# Adapters.net
KiCad netlist of a schematic drawn in Altium Designer
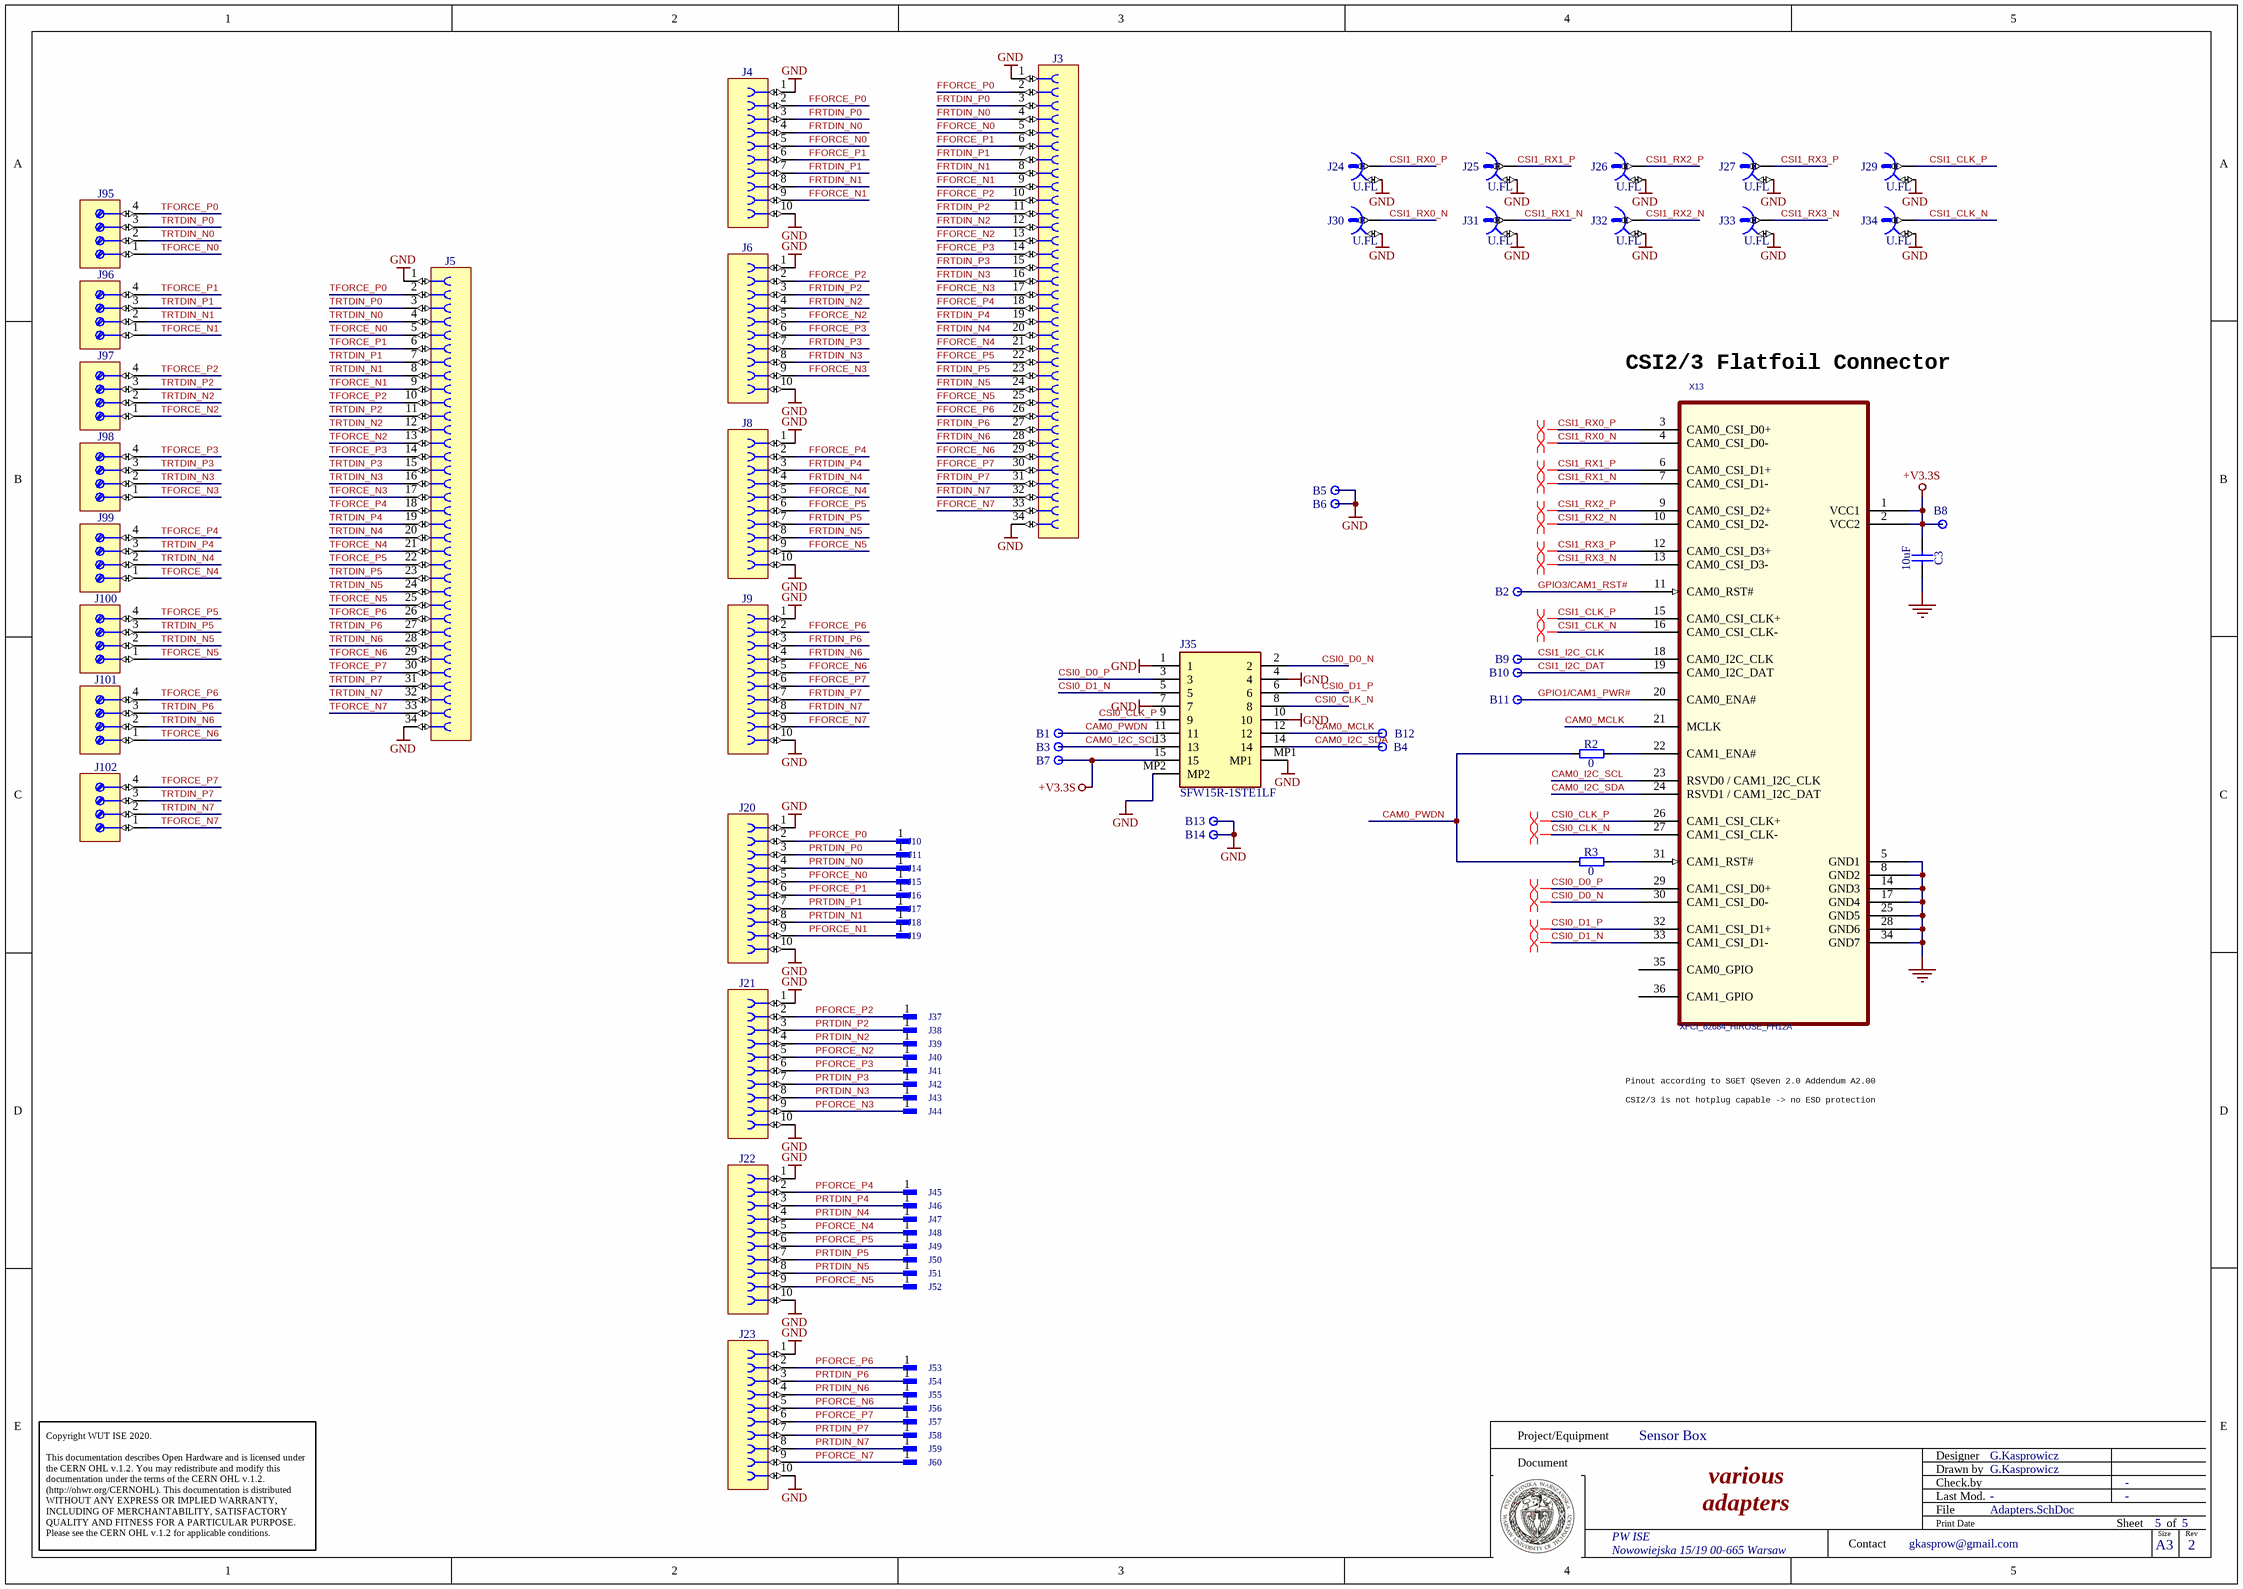
[diagram p0: Adapters.SchDoc]

(export (version "E")
  (design (tool "Eeschema 10.0.6"))
  (components
    (comp (ref "B1")
      (value "Plated Hole")
      (footprint "c130h80")
      (description "Single Terminal Socket")
      (fields (field (name "PART NUMBER") "PLATED_HOLE0.8_PAD1.3"))
      (libsource (lib "Eletro-mechanical") (part "Single Terminal Socket"))
    )
    (comp (ref "B2")
      (value "Plated Hole")
      (footprint "c130h80")
      (description "Single Terminal Socket")
      (fields (field (name "PART NUMBER") "PLATED_HOLE0.8_PAD1.3"))
      (libsource (lib "Eletro-mechanical") (part "Single Terminal Socket"))
    )
    (comp (ref "B3")
      (value "Plated Hole")
      (footprint "c130h80")
      (description "Single Terminal Socket")
      (fields (field (name "PART NUMBER") "PLATED_HOLE0.8_PAD1.3"))
      (libsource (lib "Eletro-mechanical") (part "Single Terminal Socket"))
    )
    (comp (ref "B4")
      (value "Plated Hole")
      (footprint "c130h80")
      (description "Single Terminal Socket")
      (fields (field (name "PART NUMBER") "PLATED_HOLE0.8_PAD1.3"))
      (libsource (lib "Eletro-mechanical") (part "Single Terminal Socket"))
    )
    (comp (ref "B5")
      (value "Plated Hole")
      (footprint "c130h80")
      (description "Single Terminal Socket")
      (fields (field (name "PART NUMBER") "PLATED_HOLE0.8_PAD1.3"))
      (libsource (lib "Eletro-mechanical") (part "Single Terminal Socket"))
    )
    (comp (ref "B6")
      (value "Plated Hole")
      (footprint "c130h80")
      (description "Single Terminal Socket")
      (fields (field (name "PART NUMBER") "PLATED_HOLE0.8_PAD1.3"))
      (libsource (lib "Eletro-mechanical") (part "Single Terminal Socket"))
    )
    (comp (ref "B7")
      (value "Plated Hole")
      (footprint "c130h80")
      (description "Single Terminal Socket")
      (fields (field (name "PART NUMBER") "PLATED_HOLE0.8_PAD1.3"))
      (libsource (lib "Eletro-mechanical") (part "Single Terminal Socket"))
    )
    (comp (ref "B8")
      (value "Plated Hole")
      (footprint "c130h80")
      (description "Single Terminal Socket")
      (fields (field (name "PART NUMBER") "PLATED_HOLE0.8_PAD1.3"))
      (libsource (lib "Eletro-mechanical") (part "Single Terminal Socket"))
    )
    (comp (ref "B9")
      (value "Plated Hole")
      (footprint "c130h80")
      (description "Single Terminal Socket")
      (fields (field (name "PART NUMBER") "PLATED_HOLE0.8_PAD1.3"))
      (libsource (lib "Eletro-mechanical") (part "Single Terminal Socket"))
    )
    (comp (ref "B10")
      (value "Plated Hole")
      (footprint "c130h80")
      (description "Single Terminal Socket")
      (fields (field (name "PART NUMBER") "PLATED_HOLE0.8_PAD1.3"))
      (libsource (lib "Eletro-mechanical") (part "Single Terminal Socket"))
    )
    (comp (ref "B11")
      (value "Plated Hole")
      (footprint "c130h80")
      (description "Single Terminal Socket")
      (fields (field (name "PART NUMBER") "PLATED_HOLE0.8_PAD1.3"))
      (libsource (lib "Eletro-mechanical") (part "Single Terminal Socket"))
    )
    (comp (ref "B12")
      (value "Plated Hole")
      (footprint "c130h80")
      (description "Single Terminal Socket")
      (fields (field (name "PART NUMBER") "PLATED_HOLE0.8_PAD1.3"))
      (libsource (lib "Eletro-mechanical") (part "Single Terminal Socket"))
    )
    (comp (ref "B13")
      (value "Plated Hole")
      (footprint "c130h80")
      (description "Single Terminal Socket")
      (fields (field (name "PART NUMBER") "PLATED_HOLE0.8_PAD1.3"))
      (libsource (lib "Eletro-mechanical") (part "Single Terminal Socket"))
    )
    (comp (ref "B14")
      (value "Plated Hole")
      (footprint "c130h80")
      (description "Single Terminal Socket")
      (fields (field (name "PART NUMBER") "PLATED_HOLE0.8_PAD1.3"))
      (libsource (lib "Eletro-mechanical") (part "Single Terminal Socket"))
    )
    (comp (ref "C3")
      (value "10uF")
      (footprint "CAPC2012X135N")
      (description "Non-polarised capacitor")
      (fields (field (name "PART NUMBER") "CC0805_10UF_16V_10%_X5R") (field (name "VOLTAGE") "16V"))
      (libsource (lib "Capacitors") (part "Capacitor - non polarized"))
    )
    (comp (ref "J3")
      (value "Socket 34")
      (footprint "3M_9134-4500PL")
      (description "Connector 34 Female")
      (fields (field (name "PART NUMBER") "3M_9134-4500PL") (field (name "MANUFACTURER") "3M"))
      (libsource (lib "Connectors") (part "Connector 34 Female"))
    )
    (comp (ref "J4")
      (value "FFC/FPC")
      (footprint "MOLEX_52745-1097")
      (description "Connector 10 Female")
      (fields (field (name "PART NUMBER") "MOLEX_52745-1097") (field (name "MANUFACTURER") "MOLEX"))
      (libsource (lib "Connectors") (part "Connector 10 Female"))
    )
    (comp (ref "J5")
      (value "Socket 34")
      (footprint "3M_9134-4500PL")
      (description "Connector 34 Female")
      (fields (field (name "PART NUMBER") "3M_9134-4500PL") (field (name "MANUFACTURER") "3M"))
      (libsource (lib "Connectors") (part "Connector 34 Female"))
    )
    (comp (ref "J6")
      (value "FFC/FPC")
      (footprint "MOLEX_52745-1097")
      (description "Connector 10 Female")
      (fields (field (name "PART NUMBER") "MOLEX_52745-1097") (field (name "MANUFACTURER") "MOLEX"))
      (libsource (lib "Connectors") (part "Connector 10 Female"))
    )
    (comp (ref "J8")
      (value "FFC/FPC")
      (footprint "MOLEX_52745-1097")
      (description "Connector 10 Female")
      (fields (field (name "PART NUMBER") "MOLEX_52745-1097") (field (name "MANUFACTURER") "MOLEX"))
      (libsource (lib "Connectors") (part "Connector 10 Female"))
    )
    (comp (ref "J9")
      (value "FFC/FPC")
      (footprint "MOLEX_52745-1097")
      (description "Connector 10 Female")
      (fields (field (name "PART NUMBER") "MOLEX_52745-1097") (field (name "MANUFACTURER") "MOLEX"))
      (libsource (lib "Connectors") (part "Connector 10 Female"))
    )
    (comp (ref "J10")
      (value "SMD Pad")
      (footprint "R350X200")
      (description "Single SMD Pad")
      (fields (field (name "PART NUMBER") "SMD_PAD_3.5X2MM"))
      (libsource (lib "Eletro-mechanical") (part "Single SMD Pad"))
    )
    (comp (ref "J11")
      (value "SMD Pad")
      (footprint "R350X200")
      (description "Single SMD Pad")
      (fields (field (name "PART NUMBER") "SMD_PAD_3.5X2MM"))
      (libsource (lib "Eletro-mechanical") (part "Single SMD Pad"))
    )
    (comp (ref "J14")
      (value "SMD Pad")
      (footprint "R350X200")
      (description "Single SMD Pad")
      (fields (field (name "PART NUMBER") "SMD_PAD_3.5X2MM"))
      (libsource (lib "Eletro-mechanical") (part "Single SMD Pad"))
    )
    (comp (ref "J15")
      (value "SMD Pad")
      (footprint "R350X200")
      (description "Single SMD Pad")
      (fields (field (name "PART NUMBER") "SMD_PAD_3.5X2MM"))
      (libsource (lib "Eletro-mechanical") (part "Single SMD Pad"))
    )
    (comp (ref "J16")
      (value "SMD Pad")
      (footprint "R350X200")
      (description "Single SMD Pad")
      (fields (field (name "PART NUMBER") "SMD_PAD_3.5X2MM"))
      (libsource (lib "Eletro-mechanical") (part "Single SMD Pad"))
    )
    (comp (ref "J17")
      (value "SMD Pad")
      (footprint "R350X200")
      (description "Single SMD Pad")
      (fields (field (name "PART NUMBER") "SMD_PAD_3.5X2MM"))
      (libsource (lib "Eletro-mechanical") (part "Single SMD Pad"))
    )
    (comp (ref "J18")
      (value "SMD Pad")
      (footprint "R350X200")
      (description "Single SMD Pad")
      (fields (field (name "PART NUMBER") "SMD_PAD_3.5X2MM"))
      (libsource (lib "Eletro-mechanical") (part "Single SMD Pad"))
    )
    (comp (ref "J19")
      (value "SMD Pad")
      (footprint "R350X200")
      (description "Single SMD Pad")
      (fields (field (name "PART NUMBER") "SMD_PAD_3.5X2MM"))
      (libsource (lib "Eletro-mechanical") (part "Single SMD Pad"))
    )
    (comp (ref "J20")
      (value "FFC/FPC")
      (footprint "MOLEX_52745-1097")
      (description "Connector 10 Female")
      (fields (field (name "PART NUMBER") "MOLEX_52745-1097") (field (name "MANUFACTURER") "MOLEX"))
      (libsource (lib "Connectors") (part "Connector 10 Female"))
    )
    (comp (ref "J21")
      (value "FFC/FPC")
      (footprint "MOLEX_52745-1097")
      (description "Connector 10 Female")
      (fields (field (name "PART NUMBER") "MOLEX_52745-1097") (field (name "MANUFACTURER") "MOLEX"))
      (libsource (lib "Connectors") (part "Connector 10 Female"))
    )
    (comp (ref "J22")
      (value "FFC/FPC")
      (footprint "MOLEX_52745-1097")
      (description "Connector 10 Female")
      (fields (field (name "PART NUMBER") "MOLEX_52745-1097") (field (name "MANUFACTURER") "MOLEX"))
      (libsource (lib "Connectors") (part "Connector 10 Female"))
    )
    (comp (ref "J23")
      (value "FFC/FPC")
      (footprint "MOLEX_52745-1097")
      (description "Connector 10 Female")
      (fields (field (name "PART NUMBER") "MOLEX_52745-1097") (field (name "MANUFACTURER") "MOLEX"))
      (libsource (lib "Connectors") (part "Connector 10 Female"))
    )
    (comp (ref "J24")
      (value "U.FL")
      (footprint "HIROSE_U.FL-R-SMT-1(10)")
      (fields
        (field (name "PART NUMBER") "HIROSE_U.FL-R-SMT-1(10)")
        (field (name "MANUFACTURER") "HIROSE (HRS)")
        (field (name "MANUFACTURER PART NUMBER") "U.FL-R-SMT-1(10)")
      )
      (libsource (lib "Connectors") (part "Coax_1Male_1Shield"))
    )
    (comp (ref "J25")
      (value "U.FL")
      (footprint "HIROSE_U.FL-R-SMT-1(10)")
      (fields
        (field (name "PART NUMBER") "HIROSE_U.FL-R-SMT-1(10)")
        (field (name "MANUFACTURER") "HIROSE (HRS)")
        (field (name "MANUFACTURER PART NUMBER") "U.FL-R-SMT-1(10)")
      )
      (libsource (lib "Connectors") (part "Coax_1Male_1Shield"))
    )
    (comp (ref "J26")
      (value "U.FL")
      (footprint "HIROSE_U.FL-R-SMT-1(10)")
      (fields
        (field (name "PART NUMBER") "HIROSE_U.FL-R-SMT-1(10)")
        (field (name "MANUFACTURER") "HIROSE (HRS)")
        (field (name "MANUFACTURER PART NUMBER") "U.FL-R-SMT-1(10)")
      )
      (libsource (lib "Connectors") (part "Coax_1Male_1Shield"))
    )
    (comp (ref "J27")
      (value "U.FL")
      (footprint "HIROSE_U.FL-R-SMT-1(10)")
      (fields
        (field (name "PART NUMBER") "HIROSE_U.FL-R-SMT-1(10)")
        (field (name "MANUFACTURER") "HIROSE (HRS)")
        (field (name "MANUFACTURER PART NUMBER") "U.FL-R-SMT-1(10)")
      )
      (libsource (lib "Connectors") (part "Coax_1Male_1Shield"))
    )
    (comp (ref "J29")
      (value "U.FL")
      (footprint "HIROSE_U.FL-R-SMT-1(10)")
      (fields
        (field (name "PART NUMBER") "HIROSE_U.FL-R-SMT-1(10)")
        (field (name "MANUFACTURER") "HIROSE (HRS)")
        (field (name "MANUFACTURER PART NUMBER") "U.FL-R-SMT-1(10)")
      )
      (libsource (lib "Connectors") (part "Coax_1Male_1Shield"))
    )
    (comp (ref "J30")
      (value "U.FL")
      (footprint "HIROSE_U.FL-R-SMT-1(10)")
      (fields
        (field (name "PART NUMBER") "HIROSE_U.FL-R-SMT-1(10)")
        (field (name "MANUFACTURER") "HIROSE (HRS)")
        (field (name "MANUFACTURER PART NUMBER") "U.FL-R-SMT-1(10)")
      )
      (libsource (lib "Connectors") (part "Coax_1Male_1Shield"))
    )
    (comp (ref "J31")
      (value "U.FL")
      (footprint "HIROSE_U.FL-R-SMT-1(10)")
      (fields
        (field (name "PART NUMBER") "HIROSE_U.FL-R-SMT-1(10)")
        (field (name "MANUFACTURER") "HIROSE (HRS)")
        (field (name "MANUFACTURER PART NUMBER") "U.FL-R-SMT-1(10)")
      )
      (libsource (lib "Connectors") (part "Coax_1Male_1Shield"))
    )
    (comp (ref "J32")
      (value "U.FL")
      (footprint "HIROSE_U.FL-R-SMT-1(10)")
      (fields
        (field (name "PART NUMBER") "HIROSE_U.FL-R-SMT-1(10)")
        (field (name "MANUFACTURER") "HIROSE (HRS)")
        (field (name "MANUFACTURER PART NUMBER") "U.FL-R-SMT-1(10)")
      )
      (libsource (lib "Connectors") (part "Coax_1Male_1Shield"))
    )
    (comp (ref "J33")
      (value "U.FL")
      (footprint "HIROSE_U.FL-R-SMT-1(10)")
      (fields
        (field (name "PART NUMBER") "HIROSE_U.FL-R-SMT-1(10)")
        (field (name "MANUFACTURER") "HIROSE (HRS)")
        (field (name "MANUFACTURER PART NUMBER") "U.FL-R-SMT-1(10)")
      )
      (libsource (lib "Connectors") (part "Coax_1Male_1Shield"))
    )
    (comp (ref "J34")
      (value "U.FL")
      (footprint "HIROSE_U.FL-R-SMT-1(10)")
      (fields
        (field (name "PART NUMBER") "HIROSE_U.FL-R-SMT-1(10)")
        (field (name "MANUFACTURER") "HIROSE (HRS)")
        (field (name "MANUFACTURER PART NUMBER") "U.FL-R-SMT-1(10)")
      )
      (libsource (lib "Connectors") (part "Coax_1Male_1Shield"))
    )
    (comp (ref "J35")
      (value "SFW15R-1STE1LF")
      (footprint "SamacSys:SFW15R1STE1LF")
      (description "Connector")
      (fields
        (field (name "MOUSER PART NUMBER") "649-SFW15R-1STE1LF")
        (field (name "RS PART NUMBER") "1822728")
      )
      (libsource (lib "*") (part "SFW15R-1STE1LF"))
    )
    (comp (ref "J37")
      (value "SMD Pad")
      (footprint "R350X200")
      (description "Single SMD Pad")
      (fields (field (name "PART NUMBER") "SMD_PAD_3.5X2MM"))
      (libsource (lib "Eletro-mechanical") (part "Single SMD Pad"))
    )
    (comp (ref "J38")
      (value "SMD Pad")
      (footprint "R350X200")
      (description "Single SMD Pad")
      (fields (field (name "PART NUMBER") "SMD_PAD_3.5X2MM"))
      (libsource (lib "Eletro-mechanical") (part "Single SMD Pad"))
    )
    (comp (ref "J39")
      (value "SMD Pad")
      (footprint "R350X200")
      (description "Single SMD Pad")
      (fields (field (name "PART NUMBER") "SMD_PAD_3.5X2MM"))
      (libsource (lib "Eletro-mechanical") (part "Single SMD Pad"))
    )
    (comp (ref "J40")
      (value "SMD Pad")
      (footprint "R350X200")
      (description "Single SMD Pad")
      (fields (field (name "PART NUMBER") "SMD_PAD_3.5X2MM"))
      (libsource (lib "Eletro-mechanical") (part "Single SMD Pad"))
    )
    (comp (ref "J41")
      (value "SMD Pad")
      (footprint "R350X200")
      (description "Single SMD Pad")
      (fields (field (name "PART NUMBER") "SMD_PAD_3.5X2MM"))
      (libsource (lib "Eletro-mechanical") (part "Single SMD Pad"))
    )
    (comp (ref "J42")
      (value "SMD Pad")
      (footprint "R350X200")
      (description "Single SMD Pad")
      (fields (field (name "PART NUMBER") "SMD_PAD_3.5X2MM"))
      (libsource (lib "Eletro-mechanical") (part "Single SMD Pad"))
    )
    (comp (ref "J43")
      (value "SMD Pad")
      (footprint "R350X200")
      (description "Single SMD Pad")
      (fields (field (name "PART NUMBER") "SMD_PAD_3.5X2MM"))
      (libsource (lib "Eletro-mechanical") (part "Single SMD Pad"))
    )
    (comp (ref "J44")
      (value "SMD Pad")
      (footprint "R350X200")
      (description "Single SMD Pad")
      (fields (field (name "PART NUMBER") "SMD_PAD_3.5X2MM"))
      (libsource (lib "Eletro-mechanical") (part "Single SMD Pad"))
    )
    (comp (ref "J45")
      (value "SMD Pad")
      (footprint "R350X200")
      (description "Single SMD Pad")
      (fields (field (name "PART NUMBER") "SMD_PAD_3.5X2MM"))
      (libsource (lib "Eletro-mechanical") (part "Single SMD Pad"))
    )
    (comp (ref "J46")
      (value "SMD Pad")
      (footprint "R350X200")
      (description "Single SMD Pad")
      (fields (field (name "PART NUMBER") "SMD_PAD_3.5X2MM"))
      (libsource (lib "Eletro-mechanical") (part "Single SMD Pad"))
    )
    (comp (ref "J47")
      (value "SMD Pad")
      (footprint "R350X200")
      (description "Single SMD Pad")
      (fields (field (name "PART NUMBER") "SMD_PAD_3.5X2MM"))
      (libsource (lib "Eletro-mechanical") (part "Single SMD Pad"))
    )
    (comp (ref "J48")
      (value "SMD Pad")
      (footprint "R350X200")
      (description "Single SMD Pad")
      (fields (field (name "PART NUMBER") "SMD_PAD_3.5X2MM"))
      (libsource (lib "Eletro-mechanical") (part "Single SMD Pad"))
    )
    (comp (ref "J49")
      (value "SMD Pad")
      (footprint "R350X200")
      (description "Single SMD Pad")
      (fields (field (name "PART NUMBER") "SMD_PAD_3.5X2MM"))
      (libsource (lib "Eletro-mechanical") (part "Single SMD Pad"))
    )
    (comp (ref "J50")
      (value "SMD Pad")
      (footprint "R350X200")
      (description "Single SMD Pad")
      (fields (field (name "PART NUMBER") "SMD_PAD_3.5X2MM"))
      (libsource (lib "Eletro-mechanical") (part "Single SMD Pad"))
    )
    (comp (ref "J51")
      (value "SMD Pad")
      (footprint "R350X200")
      (description "Single SMD Pad")
      (fields (field (name "PART NUMBER") "SMD_PAD_3.5X2MM"))
      (libsource (lib "Eletro-mechanical") (part "Single SMD Pad"))
    )
    (comp (ref "J52")
      (value "SMD Pad")
      (footprint "R350X200")
      (description "Single SMD Pad")
      (fields (field (name "PART NUMBER") "SMD_PAD_3.5X2MM"))
      (libsource (lib "Eletro-mechanical") (part "Single SMD Pad"))
    )
    (comp (ref "J53")
      (value "SMD Pad")
      (footprint "R350X200")
      (description "Single SMD Pad")
      (fields (field (name "PART NUMBER") "SMD_PAD_3.5X2MM"))
      (libsource (lib "Eletro-mechanical") (part "Single SMD Pad"))
    )
    (comp (ref "J54")
      (value "SMD Pad")
      (footprint "R350X200")
      (description "Single SMD Pad")
      (fields (field (name "PART NUMBER") "SMD_PAD_3.5X2MM"))
      (libsource (lib "Eletro-mechanical") (part "Single SMD Pad"))
    )
    (comp (ref "J55")
      (value "SMD Pad")
      (footprint "R350X200")
      (description "Single SMD Pad")
      (fields (field (name "PART NUMBER") "SMD_PAD_3.5X2MM"))
      (libsource (lib "Eletro-mechanical") (part "Single SMD Pad"))
    )
    (comp (ref "J56")
      (value "SMD Pad")
      (footprint "R350X200")
      (description "Single SMD Pad")
      (fields (field (name "PART NUMBER") "SMD_PAD_3.5X2MM"))
      (libsource (lib "Eletro-mechanical") (part "Single SMD Pad"))
    )
    (comp (ref "J57")
      (value "SMD Pad")
      (footprint "R350X200")
      (description "Single SMD Pad")
      (fields (field (name "PART NUMBER") "SMD_PAD_3.5X2MM"))
      (libsource (lib "Eletro-mechanical") (part "Single SMD Pad"))
    )
    (comp (ref "J58")
      (value "SMD Pad")
      (footprint "R350X200")
      (description "Single SMD Pad")
      (fields (field (name "PART NUMBER") "SMD_PAD_3.5X2MM"))
      (libsource (lib "Eletro-mechanical") (part "Single SMD Pad"))
    )
    (comp (ref "J59")
      (value "SMD Pad")
      (footprint "R350X200")
      (description "Single SMD Pad")
      (fields (field (name "PART NUMBER") "SMD_PAD_3.5X2MM"))
      (libsource (lib "Eletro-mechanical") (part "Single SMD Pad"))
    )
    (comp (ref "J60")
      (value "SMD Pad")
      (footprint "R350X200")
      (description "Single SMD Pad")
      (fields (field (name "PART NUMBER") "SMD_PAD_3.5X2MM"))
      (libsource (lib "Eletro-mechanical") (part "Single SMD Pad"))
    )
    (comp (ref "J95")
      (value "~")
      (footprint "PHOENIX_1725672")
      (description "Terminal Block, 4 Positions, Screw Connection")
      (fields (field (name "PART NUMBER") "PHOENIX_1725672") (field (name "MANUFACTURER") "PHOENIX CONTACT"))
      (libsource (lib "Connectors") (part "Terminal Block_4 Positions_Screw Connection"))
    )
    (comp (ref "J96")
      (value "~")
      (footprint "PHOENIX_1725672")
      (description "Terminal Block, 4 Positions, Screw Connection")
      (fields (field (name "PART NUMBER") "PHOENIX_1725672") (field (name "MANUFACTURER") "PHOENIX CONTACT"))
      (libsource (lib "Connectors") (part "Terminal Block_4 Positions_Screw Connection"))
    )
    (comp (ref "J97")
      (value "~")
      (footprint "PHOENIX_1725672")
      (description "Terminal Block, 4 Positions, Screw Connection")
      (fields (field (name "PART NUMBER") "PHOENIX_1725672") (field (name "MANUFACTURER") "PHOENIX CONTACT"))
      (libsource (lib "Connectors") (part "Terminal Block_4 Positions_Screw Connection"))
    )
    (comp (ref "J98")
      (value "~")
      (footprint "PHOENIX_1725672")
      (description "Terminal Block, 4 Positions, Screw Connection")
      (fields (field (name "PART NUMBER") "PHOENIX_1725672") (field (name "MANUFACTURER") "PHOENIX CONTACT"))
      (libsource (lib "Connectors") (part "Terminal Block_4 Positions_Screw Connection"))
    )
    (comp (ref "J99")
      (value "~")
      (footprint "PHOENIX_1725672")
      (description "Terminal Block, 4 Positions, Screw Connection")
      (fields (field (name "PART NUMBER") "PHOENIX_1725672") (field (name "MANUFACTURER") "PHOENIX CONTACT"))
      (libsource (lib "Connectors") (part "Terminal Block_4 Positions_Screw Connection"))
    )
    (comp (ref "J100")
      (value "~")
      (footprint "PHOENIX_1725672")
      (description "Terminal Block, 4 Positions, Screw Connection")
      (fields (field (name "PART NUMBER") "PHOENIX_1725672") (field (name "MANUFACTURER") "PHOENIX CONTACT"))
      (libsource (lib "Connectors") (part "Terminal Block_4 Positions_Screw Connection"))
    )
    (comp (ref "J101")
      (value "~")
      (footprint "PHOENIX_1725672")
      (description "Terminal Block, 4 Positions, Screw Connection")
      (fields (field (name "PART NUMBER") "PHOENIX_1725672") (field (name "MANUFACTURER") "PHOENIX CONTACT"))
      (libsource (lib "Connectors") (part "Terminal Block_4 Positions_Screw Connection"))
    )
    (comp (ref "J102")
      (value "~")
      (footprint "PHOENIX_1725672")
      (description "Terminal Block, 4 Positions, Screw Connection")
      (fields (field (name "PART NUMBER") "PHOENIX_1725672") (field (name "MANUFACTURER") "PHOENIX CONTACT"))
      (libsource (lib "Connectors") (part "Terminal Block_4 Positions_Screw Connection"))
    )
    (comp (ref "R2")
      (value "0")
      (footprint "RESC1005X40N")
      (description "Resistor")
      (fields (field (name "PART NUMBER") "R0402_0R_JUMPER") (field (name "MANUFACTURER") "GENERIC"))
      (libsource (lib "Resistors") (part "Resistor"))
    )
    (comp (ref "R3")
      (value "0")
      (footprint "RESC1005X40N")
      (description "Resistor")
      (fields (field (name "PART NUMBER") "R0402_0R_JUMPER") (field (name "MANUFACTURER") "GENERIC"))
      (libsource (lib "Resistors") (part "Resistor"))
    )
    (comp (ref "X13")
      (value "XFCI_62684_HIROSE_FH12A")
      (footprint "TYCO_3-1734592-6")
      (fields (field (name "PART_NUMBER") "41500541"))
      (libsource (lib "*") (part "SGET_CamConn_FCI_Hirose"))
    )
  )
  (nets
    (net (code "1") (name "+V3.3S") (class "Default")
      (node (ref "B7") (pin "1") (pinfunction "1_1") (pintype "bidirectional"))
      (node (ref "B8") (pin "1") (pinfunction "1_1") (pintype "bidirectional"))
      (node (ref "C3") (pin "1") (pinfunction "1_1") (pintype "passive"))
      (node (ref "J35") (pin "15") (pinfunction "15_15") (pintype "passive"))
      (node (ref "X13") (pin "1") (pinfunction "VCC1_1") (pintype "power_in"))
      (node (ref "X13") (pin "2") (pinfunction "VCC2_2") (pintype "power_in"))
    )
    (net (code "2") (name "/CAM0_I2C_SCL") (class "Default")
      (node (ref "B3") (pin "1") (pinfunction "1_1") (pintype "bidirectional"))
      (node (ref "J35") (pin "13") (pinfunction "13_13") (pintype "passive"))
      (node (ref "X13") (pin "23") (pinfunction "RSVD0_/_CAM1_I2C_CLK_23") (pintype "passive"))
    )
    (net (code "3") (name "/CAM0_I2C_SDA") (class "Default")
      (node (ref "B4") (pin "1") (pinfunction "1_1") (pintype "bidirectional"))
      (node (ref "J35") (pin "14") (pinfunction "14_14") (pintype "passive"))
      (node (ref "X13") (pin "24") (pinfunction "RSVD1_/_CAM1_I2C_DAT_24") (pintype "passive"))
    )
    (net (code "4") (name "/CAM0_MCLK") (class "Default")
      (node (ref "B12") (pin "1") (pinfunction "1_1") (pintype "bidirectional"))
      (node (ref "J35") (pin "12") (pinfunction "12_12") (pintype "passive"))
      (node (ref "X13") (pin "21") (pinfunction "MCLK_21") (pintype "passive"))
    )
    (net (code "5") (name "/CAM0_PWDN") (class "Default")
      (node (ref "B1") (pin "1") (pinfunction "1_1") (pintype "bidirectional"))
      (node (ref "J35") (pin "11") (pinfunction "11_11") (pintype "passive"))
      (node (ref "R2") (pin "1") (pinfunction "1_1") (pintype "passive"))
      (node (ref "R3") (pin "1") (pinfunction "1_1") (pintype "passive"))
    )
    (net (code "6") (name "/CSI0_CLK_N") (class "Default")
      (node (ref "J35") (pin "8") (pinfunction "8_8") (pintype "passive"))
      (node (ref "X13") (pin "27") (pinfunction "CAM1_CSI_CLK-_27") (pintype "passive"))
    )
    (net (code "7") (name "/CSI0_CLK_P") (class "Default")
      (node (ref "J35") (pin "9") (pinfunction "9_9") (pintype "passive"))
      (node (ref "X13") (pin "26") (pinfunction "CAM1_CSI_CLK+_26") (pintype "passive"))
    )
    (net (code "8") (name "/CSI0_D0_N") (class "Default")
      (node (ref "J35") (pin "2") (pinfunction "2_2") (pintype "passive"))
      (node (ref "X13") (pin "30") (pinfunction "CAM1_CSI_D0-_30") (pintype "passive"))
    )
    (net (code "9") (name "/CSI0_D0_P") (class "Default")
      (node (ref "J35") (pin "3") (pinfunction "3_3") (pintype "passive"))
      (node (ref "X13") (pin "29") (pinfunction "CAM1_CSI_D0+_29") (pintype "passive"))
    )
    (net (code "10") (name "/CSI0_D1_N") (class "Default")
      (node (ref "J35") (pin "5") (pinfunction "5_5") (pintype "passive"))
      (node (ref "X13") (pin "33") (pinfunction "CAM1_CSI_D1-_33") (pintype "passive"))
    )
    (net (code "11") (name "/CSI0_D1_P") (class "Default")
      (node (ref "J35") (pin "6") (pinfunction "6_6") (pintype "passive"))
      (node (ref "X13") (pin "32") (pinfunction "CAM1_CSI_D1+_32") (pintype "passive"))
    )
    (net (code "12") (name "/CSI1_CLK_N") (class "Default")
      (node (ref "J34") (pin "1") (pinfunction "1_1") (pintype "bidirectional"))
      (node (ref "X13") (pin "16") (pinfunction "CAM0_CSI_CLK-_16") (pintype "passive"))
    )
    (net (code "13") (name "/CSI1_CLK_P") (class "Default")
      (node (ref "J29") (pin "1") (pinfunction "1_1") (pintype "bidirectional"))
      (node (ref "X13") (pin "15") (pinfunction "CAM0_CSI_CLK+_15") (pintype "passive"))
    )
    (net (code "14") (name "/CSI1_I2C_CLK") (class "Default")
      (node (ref "B9") (pin "1") (pinfunction "1_1") (pintype "bidirectional"))
      (node (ref "X13") (pin "18") (pinfunction "CAM0_I2C_CLK_18") (pintype "passive"))
    )
    (net (code "15") (name "/CSI1_I2C_DAT") (class "Default")
      (node (ref "B10") (pin "1") (pinfunction "1_1") (pintype "bidirectional"))
      (node (ref "X13") (pin "19") (pinfunction "CAM0_I2C_DAT_19") (pintype "passive"))
    )
    (net (code "16") (name "/CSI1_RX0_N") (class "Default")
      (node (ref "J30") (pin "1") (pinfunction "1_1") (pintype "bidirectional"))
      (node (ref "X13") (pin "4") (pinfunction "CAM0_CSI_D0-_4") (pintype "passive"))
    )
    (net (code "17") (name "/CSI1_RX0_P") (class "Default")
      (node (ref "J24") (pin "1") (pinfunction "1_1") (pintype "bidirectional"))
      (node (ref "X13") (pin "3") (pinfunction "CAM0_CSI_D0+_3") (pintype "passive"))
    )
    (net (code "18") (name "/CSI1_RX1_N") (class "Default")
      (node (ref "J31") (pin "1") (pinfunction "1_1") (pintype "bidirectional"))
      (node (ref "X13") (pin "7") (pinfunction "CAM0_CSI_D1-_7") (pintype "passive"))
    )
    (net (code "19") (name "/CSI1_RX1_P") (class "Default")
      (node (ref "J25") (pin "1") (pinfunction "1_1") (pintype "bidirectional"))
      (node (ref "X13") (pin "6") (pinfunction "CAM0_CSI_D1+_6") (pintype "passive"))
    )
    (net (code "20") (name "/CSI1_RX2_N") (class "Default")
      (node (ref "J32") (pin "1") (pinfunction "1_1") (pintype "bidirectional"))
      (node (ref "X13") (pin "10") (pinfunction "CAM0_CSI_D2-_10") (pintype "passive"))
    )
    (net (code "21") (name "/CSI1_RX2_P") (class "Default")
      (node (ref "J26") (pin "1") (pinfunction "1_1") (pintype "bidirectional"))
      (node (ref "X13") (pin "9") (pinfunction "CAM0_CSI_D2+_9") (pintype "passive"))
    )
    (net (code "22") (name "/CSI1_RX3_N") (class "Default")
      (node (ref "J33") (pin "1") (pinfunction "1_1") (pintype "bidirectional"))
      (node (ref "X13") (pin "13") (pinfunction "CAM0_CSI_D3-_13") (pintype "passive"))
    )
    (net (code "23") (name "/CSI1_RX3_P") (class "Default")
      (node (ref "J27") (pin "1") (pinfunction "1_1") (pintype "bidirectional"))
      (node (ref "X13") (pin "12") (pinfunction "CAM0_CSI_D3+_12") (pintype "passive"))
    )
    (net (code "24") (name "/FFORCE_N0") (class "Default")
      (node (ref "J3") (pin "5") (pinfunction "5_5") (pintype "bidirectional"))
      (node (ref "J4") (pin "5") (pinfunction "5_5") (pintype "bidirectional"))
    )
    (net (code "25") (name "/FFORCE_N1") (class "Default")
      (node (ref "J3") (pin "9") (pinfunction "9_9") (pintype "bidirectional"))
      (node (ref "J4") (pin "9") (pinfunction "9_9") (pintype "bidirectional"))
    )
    (net (code "26") (name "/FFORCE_N2") (class "Default")
      (node (ref "J3") (pin "13") (pinfunction "13_13") (pintype "bidirectional"))
      (node (ref "J6") (pin "5") (pinfunction "5_5") (pintype "bidirectional"))
    )
    (net (code "27") (name "/FFORCE_N3") (class "Default")
      (node (ref "J3") (pin "17") (pinfunction "17_17") (pintype "bidirectional"))
      (node (ref "J6") (pin "9") (pinfunction "9_9") (pintype "bidirectional"))
    )
    (net (code "28") (name "/FFORCE_N4") (class "Default")
      (node (ref "J3") (pin "21") (pinfunction "21_21") (pintype "bidirectional"))
      (node (ref "J8") (pin "5") (pinfunction "5_5") (pintype "bidirectional"))
    )
    (net (code "29") (name "/FFORCE_N5") (class "Default")
      (node (ref "J3") (pin "25") (pinfunction "25_25") (pintype "bidirectional"))
      (node (ref "J8") (pin "9") (pinfunction "9_9") (pintype "bidirectional"))
    )
    (net (code "30") (name "/FFORCE_N6") (class "Default")
      (node (ref "J3") (pin "29") (pinfunction "29_29") (pintype "bidirectional"))
      (node (ref "J9") (pin "5") (pinfunction "5_5") (pintype "bidirectional"))
    )
    (net (code "31") (name "/FFORCE_N7") (class "Default")
      (node (ref "J3") (pin "33") (pinfunction "33_33") (pintype "bidirectional"))
      (node (ref "J9") (pin "9") (pinfunction "9_9") (pintype "bidirectional"))
    )
    (net (code "32") (name "/FFORCE_P0") (class "Default")
      (node (ref "J3") (pin "2") (pinfunction "2_2") (pintype "bidirectional"))
      (node (ref "J4") (pin "2") (pinfunction "2_2") (pintype "bidirectional"))
    )
    (net (code "33") (name "/FFORCE_P1") (class "Default")
      (node (ref "J3") (pin "6") (pinfunction "6_6") (pintype "bidirectional"))
      (node (ref "J4") (pin "6") (pinfunction "6_6") (pintype "bidirectional"))
    )
    (net (code "34") (name "/FFORCE_P2") (class "Default")
      (node (ref "J3") (pin "10") (pinfunction "10_10") (pintype "bidirectional"))
      (node (ref "J6") (pin "2") (pinfunction "2_2") (pintype "bidirectional"))
    )
    (net (code "35") (name "/FFORCE_P3") (class "Default")
      (node (ref "J3") (pin "14") (pinfunction "14_14") (pintype "bidirectional"))
      (node (ref "J6") (pin "6") (pinfunction "6_6") (pintype "bidirectional"))
    )
    (net (code "36") (name "/FFORCE_P4") (class "Default")
      (node (ref "J3") (pin "18") (pinfunction "18_18") (pintype "bidirectional"))
      (node (ref "J8") (pin "2") (pinfunction "2_2") (pintype "bidirectional"))
    )
    (net (code "37") (name "/FFORCE_P5") (class "Default")
      (node (ref "J3") (pin "22") (pinfunction "22_22") (pintype "bidirectional"))
      (node (ref "J8") (pin "6") (pinfunction "6_6") (pintype "bidirectional"))
    )
    (net (code "38") (name "/FFORCE_P6") (class "Default")
      (node (ref "J3") (pin "26") (pinfunction "26_26") (pintype "bidirectional"))
      (node (ref "J9") (pin "2") (pinfunction "2_2") (pintype "bidirectional"))
    )
    (net (code "39") (name "/FFORCE_P7") (class "Default")
      (node (ref "J3") (pin "30") (pinfunction "30_30") (pintype "bidirectional"))
      (node (ref "J9") (pin "6") (pinfunction "6_6") (pintype "bidirectional"))
    )
    (net (code "40") (name "/FRTDIN_N0") (class "Default")
      (node (ref "J3") (pin "4") (pinfunction "4_4") (pintype "bidirectional"))
      (node (ref "J4") (pin "4") (pinfunction "4_4") (pintype "bidirectional"))
    )
    (net (code "41") (name "/FRTDIN_N1") (class "Default")
      (node (ref "J3") (pin "8") (pinfunction "8_8") (pintype "bidirectional"))
      (node (ref "J4") (pin "8") (pinfunction "8_8") (pintype "bidirectional"))
    )
    (net (code "42") (name "/FRTDIN_N2") (class "Default")
      (node (ref "J3") (pin "12") (pinfunction "12_12") (pintype "bidirectional"))
      (node (ref "J6") (pin "4") (pinfunction "4_4") (pintype "bidirectional"))
    )
    (net (code "43") (name "/FRTDIN_N3") (class "Default")
      (node (ref "J3") (pin "16") (pinfunction "16_16") (pintype "bidirectional"))
      (node (ref "J6") (pin "8") (pinfunction "8_8") (pintype "bidirectional"))
    )
    (net (code "44") (name "/FRTDIN_N4") (class "Default")
      (node (ref "J3") (pin "20") (pinfunction "20_20") (pintype "bidirectional"))
      (node (ref "J8") (pin "4") (pinfunction "4_4") (pintype "bidirectional"))
    )
    (net (code "45") (name "/FRTDIN_N5") (class "Default")
      (node (ref "J3") (pin "24") (pinfunction "24_24") (pintype "bidirectional"))
      (node (ref "J8") (pin "8") (pinfunction "8_8") (pintype "bidirectional"))
    )
    (net (code "46") (name "/FRTDIN_N6") (class "Default")
      (node (ref "J3") (pin "28") (pinfunction "28_28") (pintype "bidirectional"))
      (node (ref "J9") (pin "4") (pinfunction "4_4") (pintype "bidirectional"))
    )
    (net (code "47") (name "/FRTDIN_N7") (class "Default")
      (node (ref "J3") (pin "32") (pinfunction "32_32") (pintype "bidirectional"))
      (node (ref "J9") (pin "8") (pinfunction "8_8") (pintype "bidirectional"))
    )
    (net (code "48") (name "/FRTDIN_P0") (class "Default")
      (node (ref "J3") (pin "3") (pinfunction "3_3") (pintype "bidirectional"))
      (node (ref "J4") (pin "3") (pinfunction "3_3") (pintype "bidirectional"))
    )
    (net (code "49") (name "/FRTDIN_P1") (class "Default")
      (node (ref "J3") (pin "7") (pinfunction "7_7") (pintype "bidirectional"))
      (node (ref "J4") (pin "7") (pinfunction "7_7") (pintype "bidirectional"))
    )
    (net (code "50") (name "/FRTDIN_P2") (class "Default")
      (node (ref "J3") (pin "11") (pinfunction "11_11") (pintype "bidirectional"))
      (node (ref "J6") (pin "3") (pinfunction "3_3") (pintype "bidirectional"))
    )
    (net (code "51") (name "/FRTDIN_P3") (class "Default")
      (node (ref "J3") (pin "15") (pinfunction "15_15") (pintype "bidirectional"))
      (node (ref "J6") (pin "7") (pinfunction "7_7") (pintype "bidirectional"))
    )
    (net (code "52") (name "/FRTDIN_P4") (class "Default")
      (node (ref "J3") (pin "19") (pinfunction "19_19") (pintype "bidirectional"))
      (node (ref "J8") (pin "3") (pinfunction "3_3") (pintype "bidirectional"))
    )
    (net (code "53") (name "/FRTDIN_P5") (class "Default")
      (node (ref "J3") (pin "23") (pinfunction "23_23") (pintype "bidirectional"))
      (node (ref "J8") (pin "7") (pinfunction "7_7") (pintype "bidirectional"))
    )
    (net (code "54") (name "/FRTDIN_P6") (class "Default")
      (node (ref "J3") (pin "27") (pinfunction "27_27") (pintype "bidirectional"))
      (node (ref "J9") (pin "3") (pinfunction "3_3") (pintype "bidirectional"))
    )
    (net (code "55") (name "/FRTDIN_P7") (class "Default")
      (node (ref "J3") (pin "31") (pinfunction "31_31") (pintype "bidirectional"))
      (node (ref "J9") (pin "7") (pinfunction "7_7") (pintype "bidirectional"))
    )
    (net (code "56") (name "/GPIO1{slash}CAM1_PWR#") (class "Default")
      (node (ref "B11") (pin "1") (pinfunction "1_1") (pintype "bidirectional"))
      (node (ref "X13") (pin "20") (pinfunction "CAM0_ENA#_20") (pintype "passive"))
    )
    (net (code "57") (name "/GPIO3{slash}CAM1_RST#") (class "Default")
      (node (ref "B2") (pin "1") (pinfunction "1_1") (pintype "bidirectional"))
      (node (ref "X13") (pin "11") (pinfunction "CAM0_RST#_11") (pintype "input"))
    )
    (net (code "58") (name "/PFORCE_N0") (class "Default")
      (node (ref "J15") (pin "1") (pinfunction "1_1") (pintype "bidirectional"))
      (node (ref "J20") (pin "5") (pinfunction "5_5") (pintype "bidirectional"))
    )
    (net (code "59") (name "/PFORCE_N1") (class "Default")
      (node (ref "J19") (pin "1") (pinfunction "1_1") (pintype "bidirectional"))
      (node (ref "J20") (pin "9") (pinfunction "9_9") (pintype "bidirectional"))
    )
    (net (code "60") (name "/PFORCE_N2") (class "Default")
      (node (ref "J21") (pin "5") (pinfunction "5_5") (pintype "bidirectional"))
      (node (ref "J40") (pin "1") (pinfunction "1_1") (pintype "bidirectional"))
    )
    (net (code "61") (name "/PFORCE_N3") (class "Default")
      (node (ref "J21") (pin "9") (pinfunction "9_9") (pintype "bidirectional"))
      (node (ref "J44") (pin "1") (pinfunction "1_1") (pintype "bidirectional"))
    )
    (net (code "62") (name "/PFORCE_N4") (class "Default")
      (node (ref "J22") (pin "5") (pinfunction "5_5") (pintype "bidirectional"))
      (node (ref "J48") (pin "1") (pinfunction "1_1") (pintype "bidirectional"))
    )
    (net (code "63") (name "/PFORCE_N5") (class "Default")
      (node (ref "J22") (pin "9") (pinfunction "9_9") (pintype "bidirectional"))
      (node (ref "J52") (pin "1") (pinfunction "1_1") (pintype "bidirectional"))
    )
    (net (code "64") (name "/PFORCE_N6") (class "Default")
      (node (ref "J23") (pin "5") (pinfunction "5_5") (pintype "bidirectional"))
      (node (ref "J56") (pin "1") (pinfunction "1_1") (pintype "bidirectional"))
    )
    (net (code "65") (name "/PFORCE_N7") (class "Default")
      (node (ref "J23") (pin "9") (pinfunction "9_9") (pintype "bidirectional"))
      (node (ref "J60") (pin "1") (pinfunction "1_1") (pintype "bidirectional"))
    )
    (net (code "66") (name "/PFORCE_P0") (class "Default")
      (node (ref "J10") (pin "1") (pinfunction "1_1") (pintype "bidirectional"))
      (node (ref "J20") (pin "2") (pinfunction "2_2") (pintype "bidirectional"))
    )
    (net (code "67") (name "/PFORCE_P1") (class "Default")
      (node (ref "J16") (pin "1") (pinfunction "1_1") (pintype "bidirectional"))
      (node (ref "J20") (pin "6") (pinfunction "6_6") (pintype "bidirectional"))
    )
    (net (code "68") (name "/PFORCE_P2") (class "Default")
      (node (ref "J21") (pin "2") (pinfunction "2_2") (pintype "bidirectional"))
      (node (ref "J37") (pin "1") (pinfunction "1_1") (pintype "bidirectional"))
    )
    (net (code "69") (name "/PFORCE_P3") (class "Default")
      (node (ref "J21") (pin "6") (pinfunction "6_6") (pintype "bidirectional"))
      (node (ref "J41") (pin "1") (pinfunction "1_1") (pintype "bidirectional"))
    )
    (net (code "70") (name "/PFORCE_P4") (class "Default")
      (node (ref "J22") (pin "2") (pinfunction "2_2") (pintype "bidirectional"))
      (node (ref "J45") (pin "1") (pinfunction "1_1") (pintype "bidirectional"))
    )
    (net (code "71") (name "/PFORCE_P5") (class "Default")
      (node (ref "J22") (pin "6") (pinfunction "6_6") (pintype "bidirectional"))
      (node (ref "J49") (pin "1") (pinfunction "1_1") (pintype "bidirectional"))
    )
    (net (code "72") (name "/PFORCE_P6") (class "Default")
      (node (ref "J23") (pin "2") (pinfunction "2_2") (pintype "bidirectional"))
      (node (ref "J53") (pin "1") (pinfunction "1_1") (pintype "bidirectional"))
    )
    (net (code "73") (name "/PFORCE_P7") (class "Default")
      (node (ref "J23") (pin "6") (pinfunction "6_6") (pintype "bidirectional"))
      (node (ref "J57") (pin "1") (pinfunction "1_1") (pintype "bidirectional"))
    )
    (net (code "74") (name "/PRTDIN_N0") (class "Default")
      (node (ref "J14") (pin "1") (pinfunction "1_1") (pintype "bidirectional"))
      (node (ref "J20") (pin "4") (pinfunction "4_4") (pintype "bidirectional"))
    )
    (net (code "75") (name "/PRTDIN_N1") (class "Default")
      (node (ref "J18") (pin "1") (pinfunction "1_1") (pintype "bidirectional"))
      (node (ref "J20") (pin "8") (pinfunction "8_8") (pintype "bidirectional"))
    )
    (net (code "76") (name "/PRTDIN_N2") (class "Default")
      (node (ref "J21") (pin "4") (pinfunction "4_4") (pintype "bidirectional"))
      (node (ref "J39") (pin "1") (pinfunction "1_1") (pintype "bidirectional"))
    )
    (net (code "77") (name "/PRTDIN_N3") (class "Default")
      (node (ref "J21") (pin "8") (pinfunction "8_8") (pintype "bidirectional"))
      (node (ref "J43") (pin "1") (pinfunction "1_1") (pintype "bidirectional"))
    )
    (net (code "78") (name "/PRTDIN_N4") (class "Default")
      (node (ref "J22") (pin "4") (pinfunction "4_4") (pintype "bidirectional"))
      (node (ref "J47") (pin "1") (pinfunction "1_1") (pintype "bidirectional"))
    )
    (net (code "79") (name "/PRTDIN_N5") (class "Default")
      (node (ref "J22") (pin "8") (pinfunction "8_8") (pintype "bidirectional"))
      (node (ref "J51") (pin "1") (pinfunction "1_1") (pintype "bidirectional"))
    )
    (net (code "80") (name "/PRTDIN_N6") (class "Default")
      (node (ref "J23") (pin "4") (pinfunction "4_4") (pintype "bidirectional"))
      (node (ref "J55") (pin "1") (pinfunction "1_1") (pintype "bidirectional"))
    )
    (net (code "81") (name "/PRTDIN_N7") (class "Default")
      (node (ref "J23") (pin "8") (pinfunction "8_8") (pintype "bidirectional"))
      (node (ref "J59") (pin "1") (pinfunction "1_1") (pintype "bidirectional"))
    )
    (net (code "82") (name "/PRTDIN_P0") (class "Default")
      (node (ref "J11") (pin "1") (pinfunction "1_1") (pintype "bidirectional"))
      (node (ref "J20") (pin "3") (pinfunction "3_3") (pintype "bidirectional"))
    )
    (net (code "83") (name "/PRTDIN_P1") (class "Default")
      (node (ref "J17") (pin "1") (pinfunction "1_1") (pintype "bidirectional"))
      (node (ref "J20") (pin "7") (pinfunction "7_7") (pintype "bidirectional"))
    )
    (net (code "84") (name "/PRTDIN_P2") (class "Default")
      (node (ref "J21") (pin "3") (pinfunction "3_3") (pintype "bidirectional"))
      (node (ref "J38") (pin "1") (pinfunction "1_1") (pintype "bidirectional"))
    )
    (net (code "85") (name "/PRTDIN_P3") (class "Default")
      (node (ref "J21") (pin "7") (pinfunction "7_7") (pintype "bidirectional"))
      (node (ref "J42") (pin "1") (pinfunction "1_1") (pintype "bidirectional"))
    )
    (net (code "86") (name "/PRTDIN_P4") (class "Default")
      (node (ref "J22") (pin "3") (pinfunction "3_3") (pintype "bidirectional"))
      (node (ref "J46") (pin "1") (pinfunction "1_1") (pintype "bidirectional"))
    )
    (net (code "87") (name "/PRTDIN_P5") (class "Default")
      (node (ref "J22") (pin "7") (pinfunction "7_7") (pintype "bidirectional"))
      (node (ref "J50") (pin "1") (pinfunction "1_1") (pintype "bidirectional"))
    )
    (net (code "88") (name "/PRTDIN_P6") (class "Default")
      (node (ref "J23") (pin "3") (pinfunction "3_3") (pintype "bidirectional"))
      (node (ref "J54") (pin "1") (pinfunction "1_1") (pintype "bidirectional"))
    )
    (net (code "89") (name "/PRTDIN_P7") (class "Default")
      (node (ref "J23") (pin "7") (pinfunction "7_7") (pintype "bidirectional"))
      (node (ref "J58") (pin "1") (pinfunction "1_1") (pintype "bidirectional"))
    )
    (net (code "90") (name "/TFORCE_N0") (class "Default")
      (node (ref "J5") (pin "5") (pinfunction "5_5") (pintype "bidirectional"))
      (node (ref "J95") (pin "1") (pinfunction "1_1") (pintype "bidirectional"))
    )
    (net (code "91") (name "/TFORCE_N1") (class "Default")
      (node (ref "J5") (pin "9") (pinfunction "9_9") (pintype "bidirectional"))
      (node (ref "J96") (pin "1") (pinfunction "1_1") (pintype "bidirectional"))
    )
    (net (code "92") (name "/TFORCE_N2") (class "Default")
      (node (ref "J5") (pin "13") (pinfunction "13_13") (pintype "bidirectional"))
      (node (ref "J97") (pin "1") (pinfunction "1_1") (pintype "bidirectional"))
    )
    (net (code "93") (name "/TFORCE_N3") (class "Default")
      (node (ref "J5") (pin "17") (pinfunction "17_17") (pintype "bidirectional"))
      (node (ref "J98") (pin "1") (pinfunction "1_1") (pintype "bidirectional"))
    )
    (net (code "94") (name "/TFORCE_N4") (class "Default")
      (node (ref "J5") (pin "21") (pinfunction "21_21") (pintype "bidirectional"))
      (node (ref "J99") (pin "1") (pinfunction "1_1") (pintype "bidirectional"))
    )
    (net (code "95") (name "/TFORCE_N5") (class "Default")
      (node (ref "J100") (pin "1") (pinfunction "1_1") (pintype "bidirectional"))
      (node (ref "J5") (pin "25") (pinfunction "25_25") (pintype "bidirectional"))
    )
    (net (code "96") (name "/TFORCE_N6") (class "Default")
      (node (ref "J101") (pin "1") (pinfunction "1_1") (pintype "bidirectional"))
      (node (ref "J5") (pin "29") (pinfunction "29_29") (pintype "bidirectional"))
    )
    (net (code "97") (name "/TFORCE_N7") (class "Default")
      (node (ref "J102") (pin "1") (pinfunction "1_1") (pintype "bidirectional"))
      (node (ref "J5") (pin "33") (pinfunction "33_33") (pintype "bidirectional"))
    )
    (net (code "98") (name "/TFORCE_P0") (class "Default")
      (node (ref "J5") (pin "2") (pinfunction "2_2") (pintype "bidirectional"))
      (node (ref "J95") (pin "4") (pinfunction "4_4") (pintype "bidirectional"))
    )
    (net (code "99") (name "/TFORCE_P1") (class "Default")
      (node (ref "J5") (pin "6") (pinfunction "6_6") (pintype "bidirectional"))
      (node (ref "J96") (pin "4") (pinfunction "4_4") (pintype "bidirectional"))
    )
    (net (code "100") (name "/TFORCE_P2") (class "Default")
      (node (ref "J5") (pin "10") (pinfunction "10_10") (pintype "bidirectional"))
      (node (ref "J97") (pin "4") (pinfunction "4_4") (pintype "bidirectional"))
    )
    (net (code "101") (name "/TFORCE_P3") (class "Default")
      (node (ref "J5") (pin "14") (pinfunction "14_14") (pintype "bidirectional"))
      (node (ref "J98") (pin "4") (pinfunction "4_4") (pintype "bidirectional"))
    )
    (net (code "102") (name "/TFORCE_P4") (class "Default")
      (node (ref "J5") (pin "18") (pinfunction "18_18") (pintype "bidirectional"))
      (node (ref "J99") (pin "4") (pinfunction "4_4") (pintype "bidirectional"))
    )
    (net (code "103") (name "/TFORCE_P5") (class "Default")
      (node (ref "J100") (pin "4") (pinfunction "4_4") (pintype "bidirectional"))
      (node (ref "J5") (pin "22") (pinfunction "22_22") (pintype "bidirectional"))
    )
    (net (code "104") (name "/TFORCE_P6") (class "Default")
      (node (ref "J101") (pin "4") (pinfunction "4_4") (pintype "bidirectional"))
      (node (ref "J5") (pin "26") (pinfunction "26_26") (pintype "bidirectional"))
    )
    (net (code "105") (name "/TFORCE_P7") (class "Default")
      (node (ref "J102") (pin "4") (pinfunction "4_4") (pintype "bidirectional"))
      (node (ref "J5") (pin "30") (pinfunction "30_30") (pintype "bidirectional"))
    )
    (net (code "106") (name "/TRTDIN_N0") (class "Default")
      (node (ref "J5") (pin "4") (pinfunction "4_4") (pintype "bidirectional"))
      (node (ref "J95") (pin "2") (pinfunction "2_2") (pintype "bidirectional"))
    )
    (net (code "107") (name "/TRTDIN_N1") (class "Default")
      (node (ref "J5") (pin "8") (pinfunction "8_8") (pintype "bidirectional"))
      (node (ref "J96") (pin "2") (pinfunction "2_2") (pintype "bidirectional"))
    )
    (net (code "108") (name "/TRTDIN_N2") (class "Default")
      (node (ref "J5") (pin "12") (pinfunction "12_12") (pintype "bidirectional"))
      (node (ref "J97") (pin "2") (pinfunction "2_2") (pintype "bidirectional"))
    )
    (net (code "109") (name "/TRTDIN_N3") (class "Default")
      (node (ref "J5") (pin "16") (pinfunction "16_16") (pintype "bidirectional"))
      (node (ref "J98") (pin "2") (pinfunction "2_2") (pintype "bidirectional"))
    )
    (net (code "110") (name "/TRTDIN_N4") (class "Default")
      (node (ref "J5") (pin "20") (pinfunction "20_20") (pintype "bidirectional"))
      (node (ref "J99") (pin "2") (pinfunction "2_2") (pintype "bidirectional"))
    )
    (net (code "111") (name "/TRTDIN_N5") (class "Default")
      (node (ref "J100") (pin "2") (pinfunction "2_2") (pintype "bidirectional"))
      (node (ref "J5") (pin "24") (pinfunction "24_24") (pintype "bidirectional"))
    )
    (net (code "112") (name "/TRTDIN_N6") (class "Default")
      (node (ref "J101") (pin "2") (pinfunction "2_2") (pintype "bidirectional"))
      (node (ref "J5") (pin "28") (pinfunction "28_28") (pintype "bidirectional"))
    )
    (net (code "113") (name "/TRTDIN_N7") (class "Default")
      (node (ref "J102") (pin "2") (pinfunction "2_2") (pintype "bidirectional"))
      (node (ref "J5") (pin "32") (pinfunction "32_32") (pintype "bidirectional"))
    )
    (net (code "114") (name "/TRTDIN_P0") (class "Default")
      (node (ref "J5") (pin "3") (pinfunction "3_3") (pintype "bidirectional"))
      (node (ref "J95") (pin "3") (pinfunction "3_3") (pintype "bidirectional"))
    )
    (net (code "115") (name "/TRTDIN_P1") (class "Default")
      (node (ref "J5") (pin "7") (pinfunction "7_7") (pintype "bidirectional"))
      (node (ref "J96") (pin "3") (pinfunction "3_3") (pintype "bidirectional"))
    )
    (net (code "116") (name "/TRTDIN_P2") (class "Default")
      (node (ref "J5") (pin "11") (pinfunction "11_11") (pintype "bidirectional"))
      (node (ref "J97") (pin "3") (pinfunction "3_3") (pintype "bidirectional"))
    )
    (net (code "117") (name "/TRTDIN_P3") (class "Default")
      (node (ref "J5") (pin "15") (pinfunction "15_15") (pintype "bidirectional"))
      (node (ref "J98") (pin "3") (pinfunction "3_3") (pintype "bidirectional"))
    )
    (net (code "118") (name "/TRTDIN_P4") (class "Default")
      (node (ref "J5") (pin "19") (pinfunction "19_19") (pintype "bidirectional"))
      (node (ref "J99") (pin "3") (pinfunction "3_3") (pintype "bidirectional"))
    )
    (net (code "119") (name "/TRTDIN_P5") (class "Default")
      (node (ref "J100") (pin "3") (pinfunction "3_3") (pintype "bidirectional"))
      (node (ref "J5") (pin "23") (pinfunction "23_23") (pintype "bidirectional"))
    )
    (net (code "120") (name "/TRTDIN_P6") (class "Default")
      (node (ref "J101") (pin "3") (pinfunction "3_3") (pintype "bidirectional"))
      (node (ref "J5") (pin "27") (pinfunction "27_27") (pintype "bidirectional"))
    )
    (net (code "121") (name "/TRTDIN_P7") (class "Default")
      (node (ref "J102") (pin "3") (pinfunction "3_3") (pintype "bidirectional"))
      (node (ref "J5") (pin "31") (pinfunction "31_31") (pintype "bidirectional"))
    )
    (net (code "122") (name "GND") (class "Default")
      (node (ref "B13") (pin "1") (pinfunction "1_1") (pintype "bidirectional"))
      (node (ref "B14") (pin "1") (pinfunction "1_1") (pintype "bidirectional"))
      (node (ref "B5") (pin "1") (pinfunction "1_1") (pintype "bidirectional"))
      (node (ref "B6") (pin "1") (pinfunction "1_1") (pintype "bidirectional"))
      (node (ref "C3") (pin "2") (pinfunction "2_2") (pintype "passive"))
      (node (ref "J20") (pin "1") (pinfunction "1_1") (pintype "bidirectional"))
      (node (ref "J20") (pin "10") (pinfunction "10_10") (pintype "bidirectional"))
      (node (ref "J21") (pin "1") (pinfunction "1_1") (pintype "bidirectional"))
      (node (ref "J21") (pin "10") (pinfunction "10_10") (pintype "bidirectional"))
      (node (ref "J22") (pin "1") (pinfunction "1_1") (pintype "bidirectional"))
      (node (ref "J22") (pin "10") (pinfunction "10_10") (pintype "bidirectional"))
      (node (ref "J23") (pin "1") (pinfunction "1_1") (pintype "bidirectional"))
      (node (ref "J23") (pin "10") (pinfunction "10_10") (pintype "bidirectional"))
      (node (ref "J24") (pin "2") (pinfunction "2_2") (pintype "bidirectional"))
      (node (ref "J25") (pin "2") (pinfunction "2_2") (pintype "bidirectional"))
      (node (ref "J26") (pin "2") (pinfunction "2_2") (pintype "bidirectional"))
      (node (ref "J27") (pin "2") (pinfunction "2_2") (pintype "bidirectional"))
      (node (ref "J29") (pin "2") (pinfunction "2_2") (pintype "bidirectional"))
      (node (ref "J3") (pin "1") (pinfunction "1_1") (pintype "bidirectional"))
      (node (ref "J3") (pin "34") (pinfunction "34_34") (pintype "bidirectional"))
      (node (ref "J30") (pin "2") (pinfunction "2_2") (pintype "bidirectional"))
      (node (ref "J31") (pin "2") (pinfunction "2_2") (pintype "bidirectional"))
      (node (ref "J32") (pin "2") (pinfunction "2_2") (pintype "bidirectional"))
      (node (ref "J33") (pin "2") (pinfunction "2_2") (pintype "bidirectional"))
      (node (ref "J34") (pin "2") (pinfunction "2_2") (pintype "bidirectional"))
      (node (ref "J35") (pin "1") (pinfunction "1_1") (pintype "passive"))
      (node (ref "J35") (pin "10") (pinfunction "10_10") (pintype "passive"))
      (node (ref "J35") (pin "4") (pinfunction "4_4") (pintype "passive"))
      (node (ref "J35") (pin "7") (pinfunction "7_7") (pintype "passive"))
      (node (ref "J35") (pin "MP1") (pinfunction "MP1_MP1") (pintype "passive"))
      (node (ref "J35") (pin "MP2") (pinfunction "MP2_MP2") (pintype "passive"))
      (node (ref "J4") (pin "1") (pinfunction "1_1") (pintype "bidirectional"))
      (node (ref "J4") (pin "10") (pinfunction "10_10") (pintype "bidirectional"))
      (node (ref "J5") (pin "1") (pinfunction "1_1") (pintype "bidirectional"))
      (node (ref "J5") (pin "34") (pinfunction "34_34") (pintype "bidirectional"))
      (node (ref "J6") (pin "1") (pinfunction "1_1") (pintype "bidirectional"))
      (node (ref "J6") (pin "10") (pinfunction "10_10") (pintype "bidirectional"))
      (node (ref "J8") (pin "1") (pinfunction "1_1") (pintype "bidirectional"))
      (node (ref "J8") (pin "10") (pinfunction "10_10") (pintype "bidirectional"))
      (node (ref "J9") (pin "1") (pinfunction "1_1") (pintype "bidirectional"))
      (node (ref "J9") (pin "10") (pinfunction "10_10") (pintype "bidirectional"))
      (node (ref "X13") (pin "14") (pinfunction "GND3_14") (pintype "power_in"))
      (node (ref "X13") (pin "17") (pinfunction "GND4_17") (pintype "power_in"))
      (node (ref "X13") (pin "25") (pinfunction "GND5_25") (pintype "power_in"))
      (node (ref "X13") (pin "28") (pinfunction "GND6_28") (pintype "power_in"))
      (node (ref "X13") (pin "34") (pinfunction "GND7_34") (pintype "power_in"))
      (node (ref "X13") (pin "5") (pinfunction "GND1_5") (pintype "power_in"))
      (node (ref "X13") (pin "8") (pinfunction "GND2_8") (pintype "power_in"))
    )
    (net (code "123") (name "Net-(X13-CAM1_ENA#)") (class "Default")
      (node (ref "R2") (pin "2") (pinfunction "2_2") (pintype "passive"))
      (node (ref "X13") (pin "22") (pinfunction "CAM1_ENA#_22") (pintype "passive"))
    )
    (net (code "124") (name "Net-(X13-CAM1_RST#)") (class "Default")
      (node (ref "R3") (pin "2") (pinfunction "2_2") (pintype "passive"))
      (node (ref "X13") (pin "31") (pinfunction "CAM1_RST#_31") (pintype "input"))
    )
    (net (code "125") (name "unconnected-(X13-CAM0_GPIO-Pad35)") (class "Default")
      (node (ref "X13") (pin "35") (pinfunction "CAM0_GPIO_35") (pintype "passive"))
    )
    (net (code "126") (name "unconnected-(X13-CAM1_GPIO-Pad36)") (class "Default")
      (node (ref "X13") (pin "36") (pinfunction "CAM1_GPIO_36") (pintype "passive"))
    )
  )
)
